# M_B_adapter-tssop.net
KiCad netlist of a schematic drawn in EAGLE
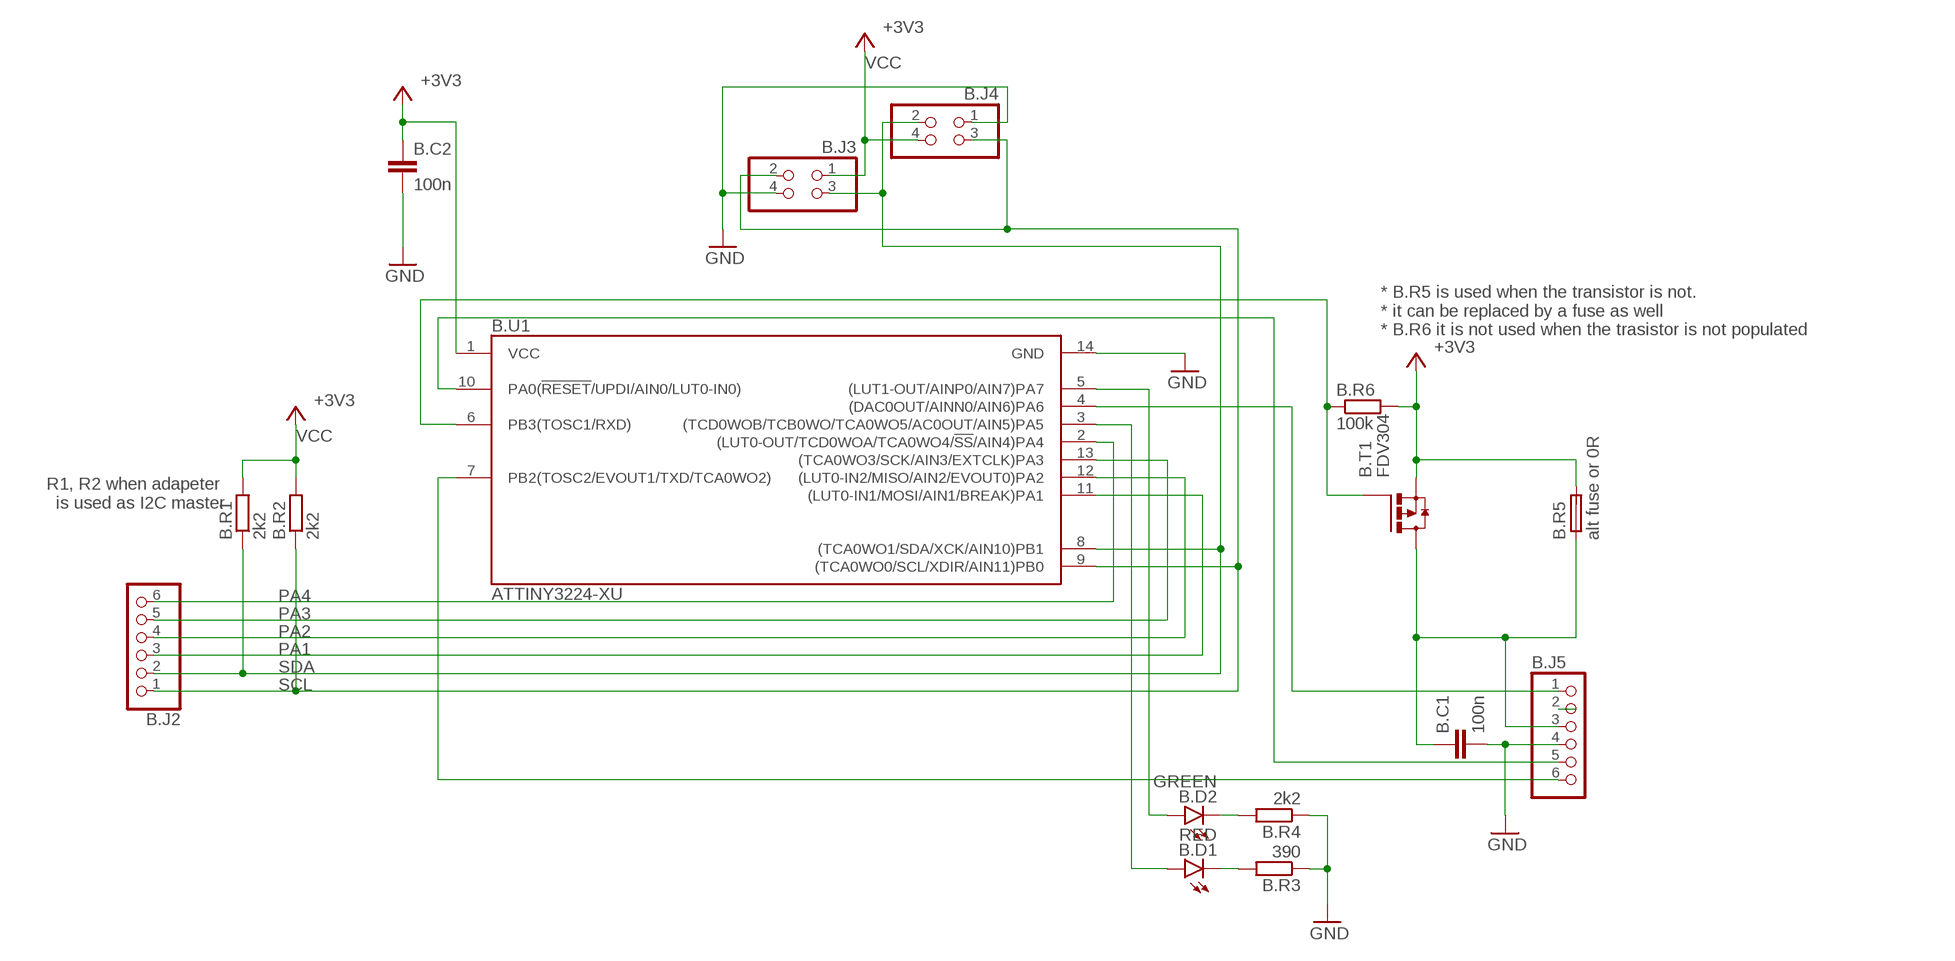
[diagram p0: schematic, sheet 1]

(export (version "E")
  (design (tool "Eeschema 10.0.6"))
  (components
    (comp (ref "B.C1")
      (value "100n")
      (footprint "eagle-import:C0603")
      (libsource (lib "eagle-import") (part "C-EUC0603"))
    )
    (comp (ref "B.C2")
      (value "100n")
      (footprint "eagle-import:C0603")
      (libsource (lib "eagle-import") (part "C-EUC0603"))
    )
    (comp (ref "B.D1")
      (value "RED")
      (footprint "eagle-import:CHIP-LED0603")
      (libsource (lib "eagle-import") (part "LEDCHIP-LED0603"))
    )
    (comp (ref "B.D2")
      (value "GREEN")
      (footprint "eagle-import:CHIP-LED0603")
      (libsource (lib "eagle-import") (part "LEDCHIP-LED0603"))
    )
    (comp (ref "B.J2")
      (value "PINHD-1X6")
      (footprint "eagle-import:1X06")
      (libsource (lib "eagle-import") (part "PINHD-1X6"))
    )
    (comp (ref "B.J3")
      (value "PINHD-2X2")
      (footprint "eagle-import:2X02")
      (libsource (lib "eagle-import") (part "PINHD-2X2"))
    )
    (comp (ref "B.J4")
      (value "PINHD-2X2")
      (footprint "eagle-import:2X02")
      (libsource (lib "eagle-import") (part "PINHD-2X2"))
    )
    (comp (ref "B.J5")
      (value "PINHD-1X6")
      (footprint "eagle-import:1X06")
      (libsource (lib "eagle-import") (part "PINHD-1X6"))
    )
    (comp (ref "B.R1")
      (value "2k2")
      (footprint "eagle-import:R0603")
      (libsource (lib "eagle-import") (part "R-EU_R0603"))
    )
    (comp (ref "B.R2")
      (value "2k2")
      (footprint "eagle-import:R0603")
      (libsource (lib "eagle-import") (part "R-EU_R0603"))
    )
    (comp (ref "B.R3")
      (value "390")
      (footprint "eagle-import:R0603")
      (libsource (lib "eagle-import") (part "R-EU_R0603"))
    )
    (comp (ref "B.R4")
      (value "2k2")
      (footprint "eagle-import:R0603")
      (libsource (lib "eagle-import") (part "R-EU_R0603"))
    )
    (comp (ref "B.R5")
      (value "alt fuse or 0R")
      (footprint "eagle-import:FUSE")
      (libsource (lib "eagle-import") (part "FUSE"))
    )
    (comp (ref "B.R6")
      (value "100k")
      (footprint "eagle-import:R0603")
      (libsource (lib "eagle-import") (part "R-EU_R0603"))
    )
    (comp (ref "B.T1")
      (value "FDV304")
      (footprint "eagle-import:SO23")
      (libsource (lib "eagle-import") (part "P-MOSFET"))
    )
    (comp (ref "B.U1")
      (value "ATTINY3224-XU")
      (footprint "eagle-import:TSSOP14")
      (libsource (lib "eagle-import") (part "ATTINY3224-XU"))
    )
  )
  (nets
    (net (code "1") (name "+3V3") (class "Default")
      (node (ref "B.C2") (pin "1") (pinfunction "1_1") (pintype "passive"))
      (node (ref "B.J3") (pin "1") (pinfunction "1_1") (pintype "passive"))
      (node (ref "B.J4") (pin "4") (pinfunction "4_4") (pintype "passive"))
      (node (ref "B.R1") (pin "2") (pinfunction "2_2") (pintype "passive"))
      (node (ref "B.R2") (pin "2") (pinfunction "2_2") (pintype "passive"))
      (node (ref "B.R5") (pin "2") (pinfunction "2_2") (pintype "passive"))
      (node (ref "B.R6") (pin "2") (pinfunction "2_2") (pintype "passive"))
      (node (ref "B.T1") (pin "S") (pinfunction "S_S") (pintype "passive"))
      (node (ref "B.U1") (pin "1") (pinfunction "VCC_1") (pintype "bidirectional"))
    )
    (net (code "2") (name "/PA1") (class "Default")
      (node (ref "B.J2") (pin "3") (pinfunction "3_3") (pintype "passive"))
      (node (ref "B.U1") (pin "11") (pinfunction "(LUT0-IN1/MOSI/AIN1/BREAK)PA1_11") (pintype "bidirectional"))
    )
    (net (code "3") (name "/PA2") (class "Default")
      (node (ref "B.J2") (pin "4") (pinfunction "4_4") (pintype "passive"))
      (node (ref "B.U1") (pin "12") (pinfunction "(LUT0-IN2/MISO/AIN2/EVOUT0)PA2_12") (pintype "bidirectional"))
    )
    (net (code "4") (name "/PA3") (class "Default")
      (node (ref "B.J2") (pin "5") (pinfunction "5_5") (pintype "passive"))
      (node (ref "B.U1") (pin "13") (pinfunction "(TCA0WO3/SCK/AIN3/EXTCLK)PA3_13") (pintype "bidirectional"))
    )
    (net (code "5") (name "/PA4") (class "Default")
      (node (ref "B.J2") (pin "6") (pinfunction "6_6") (pintype "passive"))
      (node (ref "B.U1") (pin "2") (pinfunction "(LUT0-OUT/TCD0WOA/TCA0WO4/~{SS}/AIN4)PA4_2") (pintype "bidirectional"))
    )
    (net (code "6") (name "/SCL") (class "Default")
      (node (ref "B.J2") (pin "1") (pinfunction "1_1") (pintype "passive"))
      (node (ref "B.J3") (pin "2") (pinfunction "2_2") (pintype "passive"))
      (node (ref "B.J4") (pin "3") (pinfunction "3_3") (pintype "passive"))
      (node (ref "B.R2") (pin "1") (pinfunction "1_1") (pintype "passive"))
      (node (ref "B.U1") (pin "9") (pinfunction "(TCA0WO0/SCL/XDIR/AIN11)PB0_9") (pintype "bidirectional"))
    )
    (net (code "7") (name "/SDA") (class "Default")
      (node (ref "B.J2") (pin "2") (pinfunction "2_2") (pintype "passive"))
      (node (ref "B.J3") (pin "3") (pinfunction "3_3") (pintype "passive"))
      (node (ref "B.J4") (pin "2") (pinfunction "2_2") (pintype "passive"))
      (node (ref "B.R1") (pin "1") (pinfunction "1_1") (pintype "passive"))
      (node (ref "B.U1") (pin "8") (pinfunction "(TCA0WO1/SDA/XCK/AIN10)PB1_8") (pintype "bidirectional"))
    )
    (net (code "8") (name "GND") (class "Default")
      (node (ref "B.C1") (pin "2") (pinfunction "2_2") (pintype "passive"))
      (node (ref "B.C2") (pin "2") (pinfunction "2_2") (pintype "passive"))
      (node (ref "B.J3") (pin "4") (pinfunction "4_4") (pintype "passive"))
      (node (ref "B.J4") (pin "1") (pinfunction "1_1") (pintype "passive"))
      (node (ref "B.J5") (pin "4") (pinfunction "4_4") (pintype "passive"))
      (node (ref "B.R3") (pin "1") (pinfunction "1_1") (pintype "passive"))
      (node (ref "B.R4") (pin "1") (pinfunction "1_1") (pintype "passive"))
      (node (ref "B.U1") (pin "14") (pinfunction "GND_14") (pintype "bidirectional"))
    )
    (net (code "9") (name "Net-(B.C1-Pad1)") (class "Default")
      (node (ref "B.C1") (pin "1") (pinfunction "1_1") (pintype "passive"))
      (node (ref "B.J5") (pin "3") (pinfunction "3_3") (pintype "passive"))
      (node (ref "B.R5") (pin "1") (pinfunction "1_1") (pintype "passive"))
      (node (ref "B.T1") (pin "D") (pinfunction "D_D") (pintype "passive"))
    )
    (net (code "10") (name "Net-(B.D1-A)") (class "Default")
      (node (ref "B.D1") (pin "A1") (pinfunction "A_A1") (pintype "passive"))
      (node (ref "B.U1") (pin "3") (pinfunction "(TCD0WOB/TCB0WO/TCA0WO5/AC0OUT/AIN5)PA5_3") (pintype "bidirectional"))
    )
    (net (code "11") (name "Net-(B.D1-C)") (class "Default")
      (node (ref "B.D1") (pin "C1") (pinfunction "C_C1") (pintype "passive"))
      (node (ref "B.R3") (pin "2") (pinfunction "2_2") (pintype "passive"))
    )
    (net (code "12") (name "Net-(B.D2-A)") (class "Default")
      (node (ref "B.D2") (pin "A1") (pinfunction "A_A1") (pintype "passive"))
      (node (ref "B.U1") (pin "5") (pinfunction "(LUT1-OUT/AINP0/AIN7)PA7_5") (pintype "bidirectional"))
    )
    (net (code "13") (name "Net-(B.D2-C)") (class "Default")
      (node (ref "B.D2") (pin "C1") (pinfunction "C_C1") (pintype "passive"))
      (node (ref "B.R4") (pin "2") (pinfunction "2_2") (pintype "passive"))
    )
    (net (code "14") (name "Net-(B.U1-(DAC0OUT{slash}AINN0{slash}AIN6)PA6)") (class "Default")
      (node (ref "B.J5") (pin "1") (pinfunction "1_1") (pintype "passive"))
      (node (ref "B.U1") (pin "4") (pinfunction "(DAC0OUT/AINN0/AIN6)PA6_4") (pintype "bidirectional"))
    )
    (net (code "15") (name "Net-(B.U1-PA0(~{RESET}{slash}UPDI{slash}AIN0{slash}LUT0-IN0))") (class "Default")
      (node (ref "B.J5") (pin "5") (pinfunction "5_5") (pintype "passive"))
      (node (ref "B.U1") (pin "10") (pinfunction "PA0(~{RESET}/UPDI/AIN0/LUT0-IN0)_10") (pintype "bidirectional"))
    )
    (net (code "16") (name "Net-(B.U1-PB2(TOSC2{slash}EVOUT1{slash}TXD{slash}TCA0WO2))") (class "Default")
      (node (ref "B.J5") (pin "6") (pinfunction "6_6") (pintype "passive"))
      (node (ref "B.U1") (pin "7") (pinfunction "PB2(TOSC2/EVOUT1/TXD/TCA0WO2)_7") (pintype "bidirectional"))
    )
    (net (code "17") (name "Net-(B.U1-PB3(TOSC1{slash}RXD))") (class "Default")
      (node (ref "B.R6") (pin "1") (pinfunction "1_1") (pintype "passive"))
      (node (ref "B.T1") (pin "G") (pinfunction "G_G") (pintype "passive"))
      (node (ref "B.U1") (pin "6") (pinfunction "PB3(TOSC1/RXD)_6") (pintype "bidirectional"))
    )
    (net (code "18") (name "unconnected-(B.J5-Pad2)") (class "Default")
      (node (ref "B.J5") (pin "2") (pinfunction "2_2") (pintype "passive"))
    )
  )
)
